# MotorBoard.net
KiCad netlist of a schematic drawn in Altium Designer
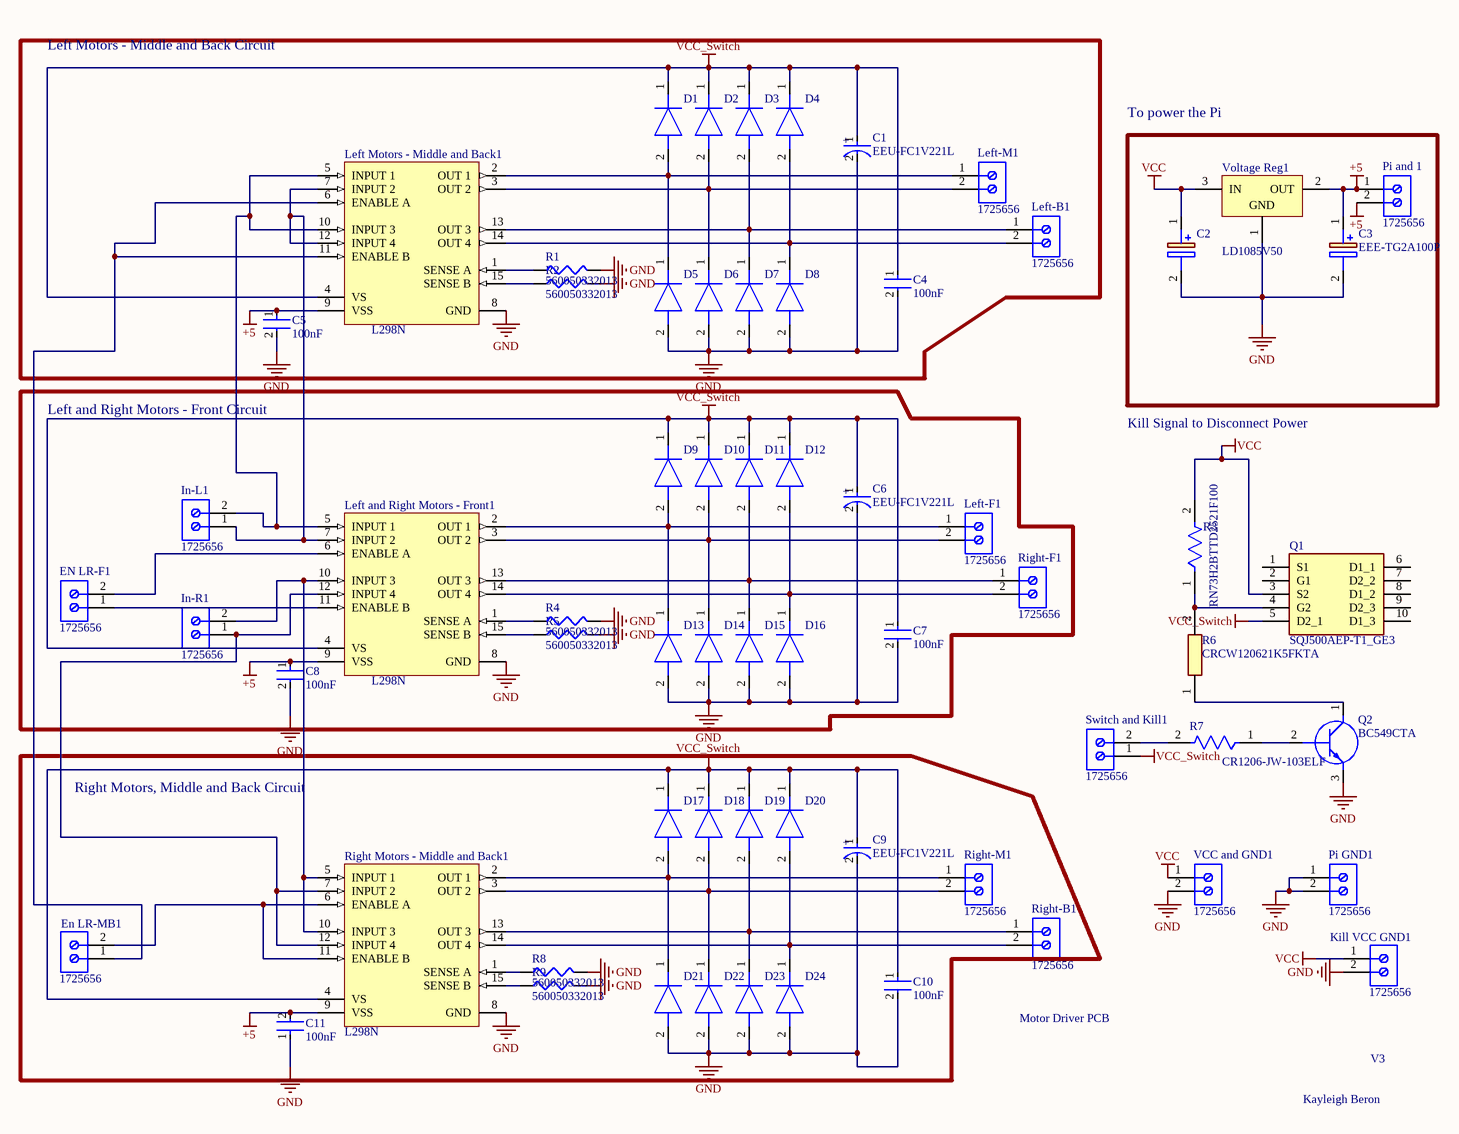
[diagram p0: MotorBoard.SchDoc]

(export (version "E")
  (design (tool "Eeschema 10.0.6"))
  (components
    (comp (ref "C1")
      (value "EEU-FC1V221L")
      (footprint "FP-EEU-FC1V221L-MFG")
      (description "CAP ALUM 220UF 20% 35V RADIAL")
      (fields
        (field (name "OCTOPART") "https://octopart.com/eeu-fc1v221l-panasonic-39478519")
        (field (name "MANUFACTURER") "Panasonic Electronic Components")
      )
      (libsource (lib "Altium Content Vault") (part "385ce6c70a3ab0aa1e866f00bd8ed49"))
    )
    (comp (ref "C2")
      (value "EEE-TG2A100P")
      (footprint "SamacSys:CAPAE830X1050N")
      (description "Capacitor Polarised")
      (fields (field (name "MOUSER PART NUMBER") "667-EEE-TG2A100P"))
      (libsource (lib "*") (part "EEE-TG2A100P"))
    )
    (comp (ref "C3")
      (value "EEE-TG2A100P")
      (footprint "SamacSys:CAPAE830X1050N")
      (description "Capacitor Polarised")
      (fields (field (name "MOUSER PART NUMBER") "667-EEE-TG2A100P"))
      (libsource (lib "*") (part "EEE-TG2A100P"))
    )
    (comp (ref "C4")
      (value "100nF")
      (footprint "FP-C2012-125-0_2-MFG")
      (description "Multilayer Ceramic Capacitors 100nF ±10% 50V X8R SMD 0805")
      (fields (field (name "TOLERANCE") "10%"))
      (libsource (lib "Altium Content Vault") (part "b4654b650e69147ec39a6b967a45e02"))
    )
    (comp (ref "C5")
      (value "100nF")
      (footprint "FP-C2012-125-0_2-MFG")
      (description "Multilayer Ceramic Capacitors 100nF ±10% 50V X8R SMD 0805")
      (fields (field (name "TOLERANCE") "10%"))
      (libsource (lib "Altium Content Vault") (part "b4654b650e69147ec39a6b967a45e02"))
    )
    (comp (ref "C6")
      (value "EEU-FC1V221L")
      (footprint "FP-EEU-FC1V221L-MFG")
      (description "CAP ALUM 220UF 20% 35V RADIAL")
      (fields
        (field (name "OCTOPART") "https://octopart.com/eeu-fc1v221l-panasonic-39478519")
        (field (name "MANUFACTURER") "Panasonic Electronic Components")
      )
      (libsource (lib "Altium Content Vault") (part "385ce6c70a3ab0aa1e866f00bd8ed49"))
    )
    (comp (ref "C7")
      (value "100nF")
      (footprint "FP-C2012-125-0_2-MFG")
      (description "Multilayer Ceramic Capacitors 100nF ±10% 50V X8R SMD 0805")
      (fields (field (name "TOLERANCE") "10%"))
      (libsource (lib "Altium Content Vault") (part "b4654b650e69147ec39a6b967a45e02"))
    )
    (comp (ref "C8")
      (value "100nF")
      (footprint "FP-C2012-125-0_2-MFG")
      (description "Multilayer Ceramic Capacitors 100nF ±10% 50V X8R SMD 0805")
      (fields (field (name "TOLERANCE") "10%"))
      (libsource (lib "Altium Content Vault") (part "b4654b650e69147ec39a6b967a45e02"))
    )
    (comp (ref "C9")
      (value "EEU-FC1V221L")
      (footprint "FP-EEU-FC1V221L-MFG")
      (description "CAP ALUM 220UF 20% 35V RADIAL")
      (fields
        (field (name "OCTOPART") "https://octopart.com/eeu-fc1v221l-panasonic-39478519")
        (field (name "MANUFACTURER") "Panasonic Electronic Components")
      )
      (libsource (lib "Altium Content Vault") (part "385ce6c70a3ab0aa1e866f00bd8ed49"))
    )
    (comp (ref "C10")
      (value "100nF")
      (footprint "FP-C2012-125-0_2-MFG")
      (description "Multilayer Ceramic Capacitors 100nF ±10% 50V X8R SMD 0805")
      (fields (field (name "TOLERANCE") "10%"))
      (libsource (lib "Altium Content Vault") (part "b4654b650e69147ec39a6b967a45e02"))
    )
    (comp (ref "C11")
      (value "100nF")
      (footprint "FP-C2012-125-0_2-MFG")
      (description "Multilayer Ceramic Capacitors 100nF ±10% 50V X8R SMD 0805")
      (fields (field (name "TOLERANCE") "10%"))
      (libsource (lib "Altium Content Vault") (part "b4654b650e69147ec39a6b967a45e02"))
    )
    (comp (ref "D1")
      (value "CMR1U-02M_TR13_PBFREE")
      (footprint "SamacSys:DIOM5226X262N")
      (description "Diode")
      (fields
        (field (name "MANUFACTURER_PART_NUMBER") "CMR1U-02M TR13 PBFREE")
        (field (name "MOUSER PART NUMBER") "610-CMR1U-02M")
      )
      (libsource (lib "*") (part "CMR1U-02M_TR13_PBFREE"))
    )
    (comp (ref "D2")
      (value "CMR1U-02M_TR13_PBFREE")
      (footprint "SamacSys:DIOM5226X262N")
      (description "Diode")
      (fields
        (field (name "MANUFACTURER_PART_NUMBER") "CMR1U-02M TR13 PBFREE")
        (field (name "MOUSER PART NUMBER") "610-CMR1U-02M")
      )
      (libsource (lib "*") (part "CMR1U-02M_TR13_PBFREE"))
    )
    (comp (ref "D3")
      (value "CMR1U-02M_TR13_PBFREE")
      (footprint "SamacSys:DIOM5226X262N")
      (description "Diode")
      (fields
        (field (name "MANUFACTURER_PART_NUMBER") "CMR1U-02M TR13 PBFREE")
        (field (name "MOUSER PART NUMBER") "610-CMR1U-02M")
      )
      (libsource (lib "*") (part "CMR1U-02M_TR13_PBFREE"))
    )
    (comp (ref "D4")
      (value "CMR1U-02M_TR13_PBFREE")
      (footprint "SamacSys:DIOM5226X262N")
      (description "Diode")
      (fields
        (field (name "MANUFACTURER_PART_NUMBER") "CMR1U-02M TR13 PBFREE")
        (field (name "MOUSER PART NUMBER") "610-CMR1U-02M")
      )
      (libsource (lib "*") (part "CMR1U-02M_TR13_PBFREE"))
    )
    (comp (ref "D5")
      (value "CMR1U-02M_TR13_PBFREE")
      (footprint "SamacSys:DIOM5226X262N")
      (description "Diode")
      (fields
        (field (name "MANUFACTURER_PART_NUMBER") "CMR1U-02M TR13 PBFREE")
        (field (name "MOUSER PART NUMBER") "610-CMR1U-02M")
      )
      (libsource (lib "*") (part "CMR1U-02M_TR13_PBFREE"))
    )
    (comp (ref "D6")
      (value "CMR1U-02M_TR13_PBFREE")
      (footprint "SamacSys:DIOM5226X262N")
      (description "Diode")
      (fields
        (field (name "MANUFACTURER_PART_NUMBER") "CMR1U-02M TR13 PBFREE")
        (field (name "MOUSER PART NUMBER") "610-CMR1U-02M")
      )
      (libsource (lib "*") (part "CMR1U-02M_TR13_PBFREE"))
    )
    (comp (ref "D7")
      (value "CMR1U-02M_TR13_PBFREE")
      (footprint "SamacSys:DIOM5226X262N")
      (description "Diode")
      (fields
        (field (name "MANUFACTURER_PART_NUMBER") "CMR1U-02M TR13 PBFREE")
        (field (name "MOUSER PART NUMBER") "610-CMR1U-02M")
      )
      (libsource (lib "*") (part "CMR1U-02M_TR13_PBFREE"))
    )
    (comp (ref "D8")
      (value "CMR1U-02M_TR13_PBFREE")
      (footprint "SamacSys:DIOM5226X262N")
      (description "Diode")
      (fields
        (field (name "MANUFACTURER_PART_NUMBER") "CMR1U-02M TR13 PBFREE")
        (field (name "MOUSER PART NUMBER") "610-CMR1U-02M")
      )
      (libsource (lib "*") (part "CMR1U-02M_TR13_PBFREE"))
    )
    (comp (ref "D9")
      (value "CMR1U-02M_TR13_PBFREE")
      (footprint "SamacSys:DIOM5226X262N")
      (description "Diode")
      (fields
        (field (name "MANUFACTURER_PART_NUMBER") "CMR1U-02M TR13 PBFREE")
        (field (name "MOUSER PART NUMBER") "610-CMR1U-02M")
      )
      (libsource (lib "*") (part "CMR1U-02M_TR13_PBFREE"))
    )
    (comp (ref "D10")
      (value "CMR1U-02M_TR13_PBFREE")
      (footprint "SamacSys:DIOM5226X262N")
      (description "Diode")
      (fields
        (field (name "MANUFACTURER_PART_NUMBER") "CMR1U-02M TR13 PBFREE")
        (field (name "MOUSER PART NUMBER") "610-CMR1U-02M")
      )
      (libsource (lib "*") (part "CMR1U-02M_TR13_PBFREE"))
    )
    (comp (ref "D11")
      (value "CMR1U-02M_TR13_PBFREE")
      (footprint "SamacSys:DIOM5226X262N")
      (description "Diode")
      (fields
        (field (name "MANUFACTURER_PART_NUMBER") "CMR1U-02M TR13 PBFREE")
        (field (name "MOUSER PART NUMBER") "610-CMR1U-02M")
      )
      (libsource (lib "*") (part "CMR1U-02M_TR13_PBFREE"))
    )
    (comp (ref "D12")
      (value "CMR1U-02M_TR13_PBFREE")
      (footprint "SamacSys:DIOM5226X262N")
      (description "Diode")
      (fields
        (field (name "MANUFACTURER_PART_NUMBER") "CMR1U-02M TR13 PBFREE")
        (field (name "MOUSER PART NUMBER") "610-CMR1U-02M")
      )
      (libsource (lib "*") (part "CMR1U-02M_TR13_PBFREE"))
    )
    (comp (ref "D13")
      (value "CMR1U-02M_TR13_PBFREE")
      (footprint "SamacSys:DIOM5226X262N")
      (description "Diode")
      (fields
        (field (name "MANUFACTURER_PART_NUMBER") "CMR1U-02M TR13 PBFREE")
        (field (name "MOUSER PART NUMBER") "610-CMR1U-02M")
      )
      (libsource (lib "*") (part "CMR1U-02M_TR13_PBFREE"))
    )
    (comp (ref "D14")
      (value "CMR1U-02M_TR13_PBFREE")
      (footprint "SamacSys:DIOM5226X262N")
      (description "Diode")
      (fields
        (field (name "MANUFACTURER_PART_NUMBER") "CMR1U-02M TR13 PBFREE")
        (field (name "MOUSER PART NUMBER") "610-CMR1U-02M")
      )
      (libsource (lib "*") (part "CMR1U-02M_TR13_PBFREE"))
    )
    (comp (ref "D15")
      (value "CMR1U-02M_TR13_PBFREE")
      (footprint "SamacSys:DIOM5226X262N")
      (description "Diode")
      (fields
        (field (name "MANUFACTURER_PART_NUMBER") "CMR1U-02M TR13 PBFREE")
        (field (name "MOUSER PART NUMBER") "610-CMR1U-02M")
      )
      (libsource (lib "*") (part "CMR1U-02M_TR13_PBFREE"))
    )
    (comp (ref "D16")
      (value "CMR1U-02M_TR13_PBFREE")
      (footprint "SamacSys:DIOM5226X262N")
      (description "Diode")
      (fields
        (field (name "MANUFACTURER_PART_NUMBER") "CMR1U-02M TR13 PBFREE")
        (field (name "MOUSER PART NUMBER") "610-CMR1U-02M")
      )
      (libsource (lib "*") (part "CMR1U-02M_TR13_PBFREE"))
    )
    (comp (ref "D17")
      (value "CMR1U-02M_TR13_PBFREE")
      (footprint "SamacSys:DIOM5226X262N")
      (description "Diode")
      (fields
        (field (name "MANUFACTURER_PART_NUMBER") "CMR1U-02M TR13 PBFREE")
        (field (name "MOUSER PART NUMBER") "610-CMR1U-02M")
      )
      (libsource (lib "*") (part "CMR1U-02M_TR13_PBFREE"))
    )
    (comp (ref "D18")
      (value "CMR1U-02M_TR13_PBFREE")
      (footprint "SamacSys:DIOM5226X262N")
      (description "Diode")
      (fields
        (field (name "MANUFACTURER_PART_NUMBER") "CMR1U-02M TR13 PBFREE")
        (field (name "MOUSER PART NUMBER") "610-CMR1U-02M")
      )
      (libsource (lib "*") (part "CMR1U-02M_TR13_PBFREE"))
    )
    (comp (ref "D19")
      (value "CMR1U-02M_TR13_PBFREE")
      (footprint "SamacSys:DIOM5226X262N")
      (description "Diode")
      (fields
        (field (name "MANUFACTURER_PART_NUMBER") "CMR1U-02M TR13 PBFREE")
        (field (name "MOUSER PART NUMBER") "610-CMR1U-02M")
      )
      (libsource (lib "*") (part "CMR1U-02M_TR13_PBFREE"))
    )
    (comp (ref "D20")
      (value "CMR1U-02M_TR13_PBFREE")
      (footprint "SamacSys:DIOM5226X262N")
      (description "Diode")
      (fields
        (field (name "MANUFACTURER_PART_NUMBER") "CMR1U-02M TR13 PBFREE")
        (field (name "MOUSER PART NUMBER") "610-CMR1U-02M")
      )
      (libsource (lib "*") (part "CMR1U-02M_TR13_PBFREE"))
    )
    (comp (ref "D21")
      (value "CMR1U-02M_TR13_PBFREE")
      (footprint "SamacSys:DIOM5226X262N")
      (description "Diode")
      (fields
        (field (name "MANUFACTURER_PART_NUMBER") "CMR1U-02M TR13 PBFREE")
        (field (name "MOUSER PART NUMBER") "610-CMR1U-02M")
      )
      (libsource (lib "*") (part "CMR1U-02M_TR13_PBFREE"))
    )
    (comp (ref "D22")
      (value "CMR1U-02M_TR13_PBFREE")
      (footprint "SamacSys:DIOM5226X262N")
      (description "Diode")
      (fields
        (field (name "MANUFACTURER_PART_NUMBER") "CMR1U-02M TR13 PBFREE")
        (field (name "MOUSER PART NUMBER") "610-CMR1U-02M")
      )
      (libsource (lib "*") (part "CMR1U-02M_TR13_PBFREE"))
    )
    (comp (ref "D23")
      (value "CMR1U-02M_TR13_PBFREE")
      (footprint "SamacSys:DIOM5226X262N")
      (description "Diode")
      (fields
        (field (name "MANUFACTURER_PART_NUMBER") "CMR1U-02M TR13 PBFREE")
        (field (name "MOUSER PART NUMBER") "610-CMR1U-02M")
      )
      (libsource (lib "*") (part "CMR1U-02M_TR13_PBFREE"))
    )
    (comp (ref "D24")
      (value "CMR1U-02M_TR13_PBFREE")
      (footprint "SamacSys:DIOM5226X262N")
      (description "Diode")
      (fields
        (field (name "MANUFACTURER_PART_NUMBER") "CMR1U-02M TR13 PBFREE")
        (field (name "MOUSER PART NUMBER") "610-CMR1U-02M")
      )
      (libsource (lib "*") (part "CMR1U-02M_TR13_PBFREE"))
    )
    (comp (ref "EN LR-F1")
      (value "1725656")
      (footprint "PHOE-1725656-2")
      (description "Male Header, Pitch 2.54 mm, 1 x 2 Position, Height 9 mm, Tail Length 3.5 mm")
      (fields (field (name "MANUFACTURER") "Phoenix Contact"))
      (libsource (lib "Altium Content Vault") (part "CN-1P-F-TB2"))
    )
    (comp (ref "En LR-MB1")
      (value "1725656")
      (footprint "PHOE-1725656-2")
      (description "Male Header, Pitch 2.54 mm, 1 x 2 Position, Height 9 mm, Tail Length 3.5 mm")
      (fields (field (name "MANUFACTURER") "Phoenix Contact"))
      (libsource (lib "Altium Content Vault") (part "CN-1P-F-TB2"))
    )
    (comp (ref "In-L1")
      (value "1725656")
      (footprint "PHOE-1725656-2")
      (description "Male Header, Pitch 2.54 mm, 1 x 2 Position, Height 9 mm, Tail Length 3.5 mm")
      (fields (field (name "MANUFACTURER") "Phoenix Contact"))
      (libsource (lib "Altium Content Vault") (part "CN-1P-F-TB2"))
    )
    (comp (ref "In-R1")
      (value "1725656")
      (footprint "PHOE-1725656-2")
      (description "Male Header, Pitch 2.54 mm, 1 x 2 Position, Height 9 mm, Tail Length 3.5 mm")
      (fields (field (name "MANUFACTURER") "Phoenix Contact"))
      (libsource (lib "Altium Content Vault") (part "CN-1P-F-TB2"))
    )
    (comp (ref "Kill VCC GND1")
      (value "1725656")
      (footprint "PHOE-1725656-2")
      (description "Male Header, Pitch 2.54 mm, 1 x 2 Position, Height 9 mm, Tail Length 3.5 mm")
      (fields (field (name "MANUFACTURER") "Phoenix Contact"))
      (libsource (lib "Altium Content Vault") (part "CN-1P-F-TB2"))
    )
    (comp (ref "Left and Right Motors - Front1")
      (value "L298N")
      (footprint "STM-FM-15")
      (description "Dual Full-Bridge Driver, 4.8 to 46 V, -40 to 150 degC, 15-Pin FM (MW 15L), RoHS, Tube")
      (fields (field (name "MANUFACTURER") "STMicroelectronics") (field (name "PARTNUMBER") "L298"))
      (libsource (lib "Altium Content Vault") (part "STM-L298-15"))
    )
    (comp (ref "Left Motors - Middle and Back1")
      (value "L298N")
      (footprint "STM-FM-15")
      (description "Dual Full-Bridge Driver, 4.8 to 46 V, -40 to 150 degC, 15-Pin FM (MW 15L), RoHS, Tube")
      (fields (field (name "MANUFACTURER") "STMicroelectronics") (field (name "PARTNUMBER") "L298"))
      (libsource (lib "Altium Content Vault") (part "STM-L298-15"))
    )
    (comp (ref "Left-B1")
      (value "1725656")
      (footprint "PHOE-1725656-2")
      (description "Male Header, Pitch 2.54 mm, 1 x 2 Position, Height 9 mm, Tail Length 3.5 mm")
      (fields (field (name "MANUFACTURER") "Phoenix Contact"))
      (libsource (lib "Altium Content Vault") (part "CN-1P-F-TB2"))
    )
    (comp (ref "Left-F1")
      (value "1725656")
      (footprint "PHOE-1725656-2")
      (description "Male Header, Pitch 2.54 mm, 1 x 2 Position, Height 9 mm, Tail Length 3.5 mm")
      (fields (field (name "MANUFACTURER") "Phoenix Contact"))
      (libsource (lib "Altium Content Vault") (part "CN-1P-F-TB2"))
    )
    (comp (ref "Left-M1")
      (value "1725656")
      (footprint "PHOE-1725656-2")
      (description "Male Header, Pitch 2.54 mm, 1 x 2 Position, Height 9 mm, Tail Length 3.5 mm")
      (fields (field (name "MANUFACTURER") "Phoenix Contact"))
      (libsource (lib "Altium Content Vault") (part "CN-1P-F-TB2"))
    )
    (comp (ref "Pi and 1")
      (value "1725656")
      (footprint "PHOE-1725656-2")
      (description "Male Header, Pitch 2.54 mm, 1 x 2 Position, Height 9 mm, Tail Length 3.5 mm")
      (fields (field (name "MANUFACTURER") "Phoenix Contact"))
      (libsource (lib "Altium Content Vault") (part "CN-1P-F-TB2"))
    )
    (comp (ref "Pi GND1")
      (value "1725656")
      (footprint "PHOE-1725656-2")
      (description "Male Header, Pitch 2.54 mm, 1 x 2 Position, Height 9 mm, Tail Length 3.5 mm")
      (fields (field (name "MANUFACTURER") "Phoenix Contact"))
      (libsource (lib "Altium Content Vault") (part "CN-1P-F-TB2"))
    )
    (comp (ref "Q1")
      (value "SQJ500AEP-T1_GE3")
      (footprint "SamacSys:SQJB02ELPT1_GE3")
      (description "MOSFET (N-Channel)")
      (fields (field (name "MOUSER PART NUMBER") "78-SQJ500AEP-T1_GE3"))
      (libsource (lib "*") (part "SQJ500AEP-T1_GE3"))
    )
    (comp (ref "Q2")
      (value "BC549CTA")
      (footprint "SamacSys:BC33740TA")
      (description "Transistor BJT NPN")
      (fields (field (name "MOUSER PART NUMBER") "512-BC549CTA"))
      (libsource (lib "*") (part "BC549CTA"))
    )
    (comp (ref "R1")
      (value "560050332013")
      (footprint "WRIS-KSKE_1206_L3.1W1.6H0.6")
      (description "560050332013 Res, R5, 1%, 0.5W, Thick Film, 1206 Rohs Compliant: Yes")
      (libsource (lib "Altium Content Vault") (part "Resistor"))
    )
    (comp (ref "R2")
      (value "560050332013")
      (footprint "WRIS-KSKE_1206_L3.1W1.6H0.6")
      (description "560050332013 Res, R5, 1%, 0.5W, Thick Film, 1206 Rohs Compliant: Yes")
      (libsource (lib "Altium Content Vault") (part "Resistor"))
    )
    (comp (ref "R3")
      (value "RN73H2BTTD2521F100")
      (footprint "FP-CR1206-IPC_B")
      (description "Thick Film Chip Resistors 1206 10kΩ 0.25W 5% 200ppm/°C")
      (fields (field (name "TOLERANCE") "5%"))
      (libsource (lib "Altium Content Vault") (part "1029c3af85768c4190bb7ad29bc67b5"))
    )
    (comp (ref "R4")
      (value "560050332013")
      (footprint "WRIS-KSKE_1206_L3.1W1.6H0.6")
      (description "560050332013 Res, R5, 1%, 0.5W, Thick Film, 1206 Rohs Compliant: Yes")
      (libsource (lib "Altium Content Vault") (part "Resistor"))
    )
    (comp (ref "R5")
      (value "560050332013")
      (footprint "WRIS-KSKE_1206_L3.1W1.6H0.6")
      (description "560050332013 Res, R5, 1%, 0.5W, Thick Film, 1206 Rohs Compliant: Yes")
      (libsource (lib "Altium Content Vault") (part "Resistor"))
    )
    (comp (ref "R6")
      (value "CRCW120621K5FKTA")
      (footprint "SamacSys:RESC3216X60N")
      (description "Resistor")
      (fields (field (name "MOUSER PART NUMBER") "71-CRCW1206-21.5K"))
      (libsource (lib "*") (part "CRCW120621K5FKTA"))
    )
    (comp (ref "R7")
      (value "CR1206-JW-103ELF")
      (footprint "FP-CR1206-IPC_B")
      (description "Thick Film Chip Resistors 1206 10kΩ 0.25W 5% 200ppm/°C")
      (fields (field (name "TOLERANCE") "5%"))
      (libsource (lib "Altium Content Vault") (part "1029c3af85768c4190bb7ad29bc67b5"))
    )
    (comp (ref "R8")
      (value "560050332013")
      (footprint "WRIS-KSKE_1206_L3.1W1.6H0.6")
      (description "560050332013 Res, R5, 1%, 0.5W, Thick Film, 1206 Rohs Compliant: Yes")
      (libsource (lib "Altium Content Vault") (part "Resistor"))
    )
    (comp (ref "R9")
      (value "560050332013")
      (footprint "WRIS-KSKE_1206_L3.1W1.6H0.6")
      (description "560050332013 Res, R5, 1%, 0.5W, Thick Film, 1206 Rohs Compliant: Yes")
      (libsource (lib "Altium Content Vault") (part "Resistor"))
    )
    (comp (ref "Right Motors - Middle and Back1")
      (value "L298N")
      (footprint "STM-FM-15")
      (description "Dual Full-Bridge Driver, 4.8 to 46 V, -40 to 150 degC, 15-Pin FM (MW 15L), RoHS, Tube")
      (fields (field (name "MANUFACTURER") "STMicroelectronics") (field (name "PARTNUMBER") "L298"))
      (libsource (lib "Altium Content Vault") (part "STM-L298-15"))
    )
    (comp (ref "Right-B1")
      (value "1725656")
      (footprint "PHOE-1725656-2")
      (description "Male Header, Pitch 2.54 mm, 1 x 2 Position, Height 9 mm, Tail Length 3.5 mm")
      (fields (field (name "MANUFACTURER") "Phoenix Contact"))
      (libsource (lib "Altium Content Vault") (part "CN-1P-F-TB2"))
    )
    (comp (ref "Right-F1")
      (value "1725656")
      (footprint "PHOE-1725656-2")
      (description "Male Header, Pitch 2.54 mm, 1 x 2 Position, Height 9 mm, Tail Length 3.5 mm")
      (fields (field (name "MANUFACTURER") "Phoenix Contact"))
      (libsource (lib "Altium Content Vault") (part "CN-1P-F-TB2"))
    )
    (comp (ref "Right-M1")
      (value "1725656")
      (footprint "PHOE-1725656-2")
      (description "Male Header, Pitch 2.54 mm, 1 x 2 Position, Height 9 mm, Tail Length 3.5 mm")
      (fields (field (name "MANUFACTURER") "Phoenix Contact"))
      (libsource (lib "Altium Content Vault") (part "CN-1P-F-TB2"))
    )
    (comp (ref "Switch and Kill1")
      (value "1725656")
      (footprint "PHOE-1725656-2")
      (description "Male Header, Pitch 2.54 mm, 1 x 2 Position, Height 9 mm, Tail Length 3.5 mm")
      (fields (field (name "MANUFACTURER") "Phoenix Contact"))
      (libsource (lib "Altium Content Vault") (part "CN-1P-F-TB2"))
    )
    (comp (ref "VCC and GND1")
      (value "1725656")
      (footprint "PHOE-1725656-2")
      (description "Male Header, Pitch 2.54 mm, 1 x 2 Position, Height 9 mm, Tail Length 3.5 mm")
      (fields (field (name "MANUFACTURER") "Phoenix Contact"))
      (libsource (lib "Altium Content Vault") (part "CN-1P-F-TB2"))
    )
    (comp (ref "Voltage Reg1")
      (value "LD1085V50")
      (footprint "TO220")
      (description "3A, Low Drop Positive Voltage Regulator, 5V, 3-Pin TO-220")
      (libsource (lib "Altium Content Vault") (part "PM-REG-LD1085-SIL3"))
    )
  )
  (nets
    (net (code "1") (name "+5") (class "Default")
      (node (ref "C11") (pin "2") (pinfunction "2_2") (pintype "passive"))
      (node (ref "C3") (pin "1") (pinfunction "+_1") (pintype "passive"))
      (node (ref "C5") (pin "1") (pinfunction "1_1") (pintype "passive"))
      (node (ref "C8") (pin "1") (pinfunction "1_1") (pintype "passive"))
      (node (ref "Left Motors - Middle and Back1") (pin "9") (pinfunction "VSS_9") (pintype "power_in"))
      (node (ref "Left and Right Motors - Front1") (pin "9") (pinfunction "VSS_9") (pintype "power_in"))
      (node (ref "Pi and 1") (pin "1") (pinfunction "1_1") (pintype "passive"))
      (node (ref "Pi and 1") (pin "2") (pinfunction "2_2") (pintype "passive"))
      (node (ref "Right Motors - Middle and Back1") (pin "9") (pinfunction "VSS_9") (pintype "power_in"))
      (node (ref "Voltage Reg1") (pin "2") (pinfunction "OUT_2") (pintype "power_in"))
    )
    (net (code "2") (name "GND") (class "Default")
      (node (ref "C1") (pin "2") (pinfunction "A_2") (pintype "passive"))
      (node (ref "C10") (pin "2") (pinfunction "2_2") (pintype "passive"))
      (node (ref "C11") (pin "1") (pinfunction "1_1") (pintype "passive"))
      (node (ref "C2") (pin "2") (pinfunction "-_2") (pintype "passive"))
      (node (ref "C3") (pin "2") (pinfunction "-_2") (pintype "passive"))
      (node (ref "C4") (pin "2") (pinfunction "2_2") (pintype "passive"))
      (node (ref "C5") (pin "2") (pinfunction "2_2") (pintype "passive"))
      (node (ref "C6") (pin "2") (pinfunction "A_2") (pintype "passive"))
      (node (ref "C7") (pin "2") (pinfunction "2_2") (pintype "passive"))
      (node (ref "C8") (pin "2") (pinfunction "2_2") (pintype "passive"))
      (node (ref "C9") (pin "2") (pinfunction "A_2") (pintype "passive"))
      (node (ref "D13") (pin "2") (pinfunction "A_2") (pintype "passive"))
      (node (ref "D14") (pin "2") (pinfunction "A_2") (pintype "passive"))
      (node (ref "D15") (pin "2") (pinfunction "A_2") (pintype "passive"))
      (node (ref "D16") (pin "2") (pinfunction "A_2") (pintype "passive"))
      (node (ref "D21") (pin "2") (pinfunction "A_2") (pintype "passive"))
      (node (ref "D22") (pin "2") (pinfunction "A_2") (pintype "passive"))
      (node (ref "D23") (pin "2") (pinfunction "A_2") (pintype "passive"))
      (node (ref "D24") (pin "2") (pinfunction "A_2") (pintype "passive"))
      (node (ref "D5") (pin "2") (pinfunction "A_2") (pintype "passive"))
      (node (ref "D6") (pin "2") (pinfunction "A_2") (pintype "passive"))
      (node (ref "D7") (pin "2") (pinfunction "A_2") (pintype "passive"))
      (node (ref "D8") (pin "2") (pinfunction "A_2") (pintype "passive"))
      (node (ref "Kill VCC GND1") (pin "2") (pinfunction "2_2") (pintype "passive"))
      (node (ref "Left Motors - Middle and Back1") (pin "8") (pinfunction "GND_8") (pintype "power_in"))
      (node (ref "Left and Right Motors - Front1") (pin "8") (pinfunction "GND_8") (pintype "power_in"))
      (node (ref "Pi GND1") (pin "1") (pinfunction "1_1") (pintype "passive"))
      (node (ref "Pi GND1") (pin "2") (pinfunction "2_2") (pintype "passive"))
      (node (ref "Q2") (pin "3") (pinfunction "E_3") (pintype "passive"))
      (node (ref "R1") (pin "2") (pinfunction "2_2") (pintype "passive"))
      (node (ref "R2") (pin "2") (pinfunction "2_2") (pintype "passive"))
      (node (ref "R4") (pin "2") (pinfunction "2_2") (pintype "passive"))
      (node (ref "R5") (pin "2") (pinfunction "2_2") (pintype "passive"))
      (node (ref "R8") (pin "2") (pinfunction "2_2") (pintype "passive"))
      (node (ref "R9") (pin "2") (pinfunction "2_2") (pintype "passive"))
      (node (ref "Right Motors - Middle and Back1") (pin "8") (pinfunction "GND_8") (pintype "power_in"))
      (node (ref "VCC and GND1") (pin "2") (pinfunction "2_2") (pintype "passive"))
      (node (ref "Voltage Reg1") (pin "1") (pinfunction "GND_1") (pintype "power_in"))
    )
    (net (code "3") (name "Net-(D1-A)") (class "Default")
      (node (ref "D1") (pin "2") (pinfunction "A_2") (pintype "passive"))
      (node (ref "D5") (pin "1") (pinfunction "K_1") (pintype "passive"))
      (node (ref "Left Motors - Middle and Back1") (pin "2") (pinfunction "OUT_1_2") (pintype "output"))
      (node (ref "Left-M1") (pin "1") (pinfunction "1_1") (pintype "passive"))
    )
    (net (code "4") (name "Net-(D2-A)") (class "Default")
      (node (ref "D2") (pin "2") (pinfunction "A_2") (pintype "passive"))
      (node (ref "D6") (pin "1") (pinfunction "K_1") (pintype "passive"))
      (node (ref "Left Motors - Middle and Back1") (pin "3") (pinfunction "OUT_2_3") (pintype "output"))
      (node (ref "Left-M1") (pin "2") (pinfunction "2_2") (pintype "passive"))
    )
    (net (code "5") (name "Net-(D3-A)") (class "Default")
      (node (ref "D3") (pin "2") (pinfunction "A_2") (pintype "passive"))
      (node (ref "D7") (pin "1") (pinfunction "K_1") (pintype "passive"))
      (node (ref "Left Motors - Middle and Back1") (pin "13") (pinfunction "OUT_3_13") (pintype "output"))
      (node (ref "Left-B1") (pin "1") (pinfunction "1_1") (pintype "passive"))
    )
    (net (code "6") (name "Net-(D4-A)") (class "Default")
      (node (ref "D4") (pin "2") (pinfunction "A_2") (pintype "passive"))
      (node (ref "D8") (pin "1") (pinfunction "K_1") (pintype "passive"))
      (node (ref "Left Motors - Middle and Back1") (pin "14") (pinfunction "OUT_4_14") (pintype "output"))
      (node (ref "Left-B1") (pin "2") (pinfunction "2_2") (pintype "passive"))
    )
    (net (code "7") (name "Net-(D10-A)") (class "Default")
      (node (ref "D10") (pin "2") (pinfunction "A_2") (pintype "passive"))
      (node (ref "D14") (pin "1") (pinfunction "K_1") (pintype "passive"))
      (node (ref "Left and Right Motors - Front1") (pin "3") (pinfunction "OUT_2_3") (pintype "output"))
      (node (ref "Left-F1") (pin "2") (pinfunction "2_2") (pintype "passive"))
    )
    (net (code "8") (name "Net-(D11-A)") (class "Default")
      (node (ref "D11") (pin "2") (pinfunction "A_2") (pintype "passive"))
      (node (ref "D15") (pin "1") (pinfunction "K_1") (pintype "passive"))
      (node (ref "Left and Right Motors - Front1") (pin "13") (pinfunction "OUT_3_13") (pintype "output"))
      (node (ref "Right-F1") (pin "1") (pinfunction "1_1") (pintype "passive"))
    )
    (net (code "9") (name "Net-(D12-A)") (class "Default")
      (node (ref "D12") (pin "2") (pinfunction "A_2") (pintype "passive"))
      (node (ref "D16") (pin "1") (pinfunction "K_1") (pintype "passive"))
      (node (ref "Left and Right Motors - Front1") (pin "14") (pinfunction "OUT_4_14") (pintype "output"))
      (node (ref "Right-F1") (pin "2") (pinfunction "2_2") (pintype "passive"))
    )
    (net (code "10") (name "Net-(D13-K)") (class "Default")
      (node (ref "D13") (pin "1") (pinfunction "K_1") (pintype "passive"))
      (node (ref "D9") (pin "2") (pinfunction "A_2") (pintype "passive"))
      (node (ref "Left and Right Motors - Front1") (pin "2") (pinfunction "OUT_1_2") (pintype "output"))
      (node (ref "Left-F1") (pin "1") (pinfunction "1_1") (pintype "passive"))
    )
    (net (code "11") (name "Net-(D17-A)") (class "Default")
      (node (ref "D17") (pin "2") (pinfunction "A_2") (pintype "passive"))
      (node (ref "D21") (pin "1") (pinfunction "K_1") (pintype "passive"))
      (node (ref "Right Motors - Middle and Back1") (pin "2") (pinfunction "OUT_1_2") (pintype "output"))
      (node (ref "Right-M1") (pin "1") (pinfunction "1_1") (pintype "passive"))
    )
    (net (code "12") (name "Net-(D18-A)") (class "Default")
      (node (ref "D18") (pin "2") (pinfunction "A_2") (pintype "passive"))
      (node (ref "D22") (pin "1") (pinfunction "K_1") (pintype "passive"))
      (node (ref "Right Motors - Middle and Back1") (pin "3") (pinfunction "OUT_2_3") (pintype "output"))
      (node (ref "Right-M1") (pin "2") (pinfunction "2_2") (pintype "passive"))
    )
    (net (code "13") (name "Net-(D19-A)") (class "Default")
      (node (ref "D19") (pin "2") (pinfunction "A_2") (pintype "passive"))
      (node (ref "D23") (pin "1") (pinfunction "K_1") (pintype "passive"))
      (node (ref "Right Motors - Middle and Back1") (pin "13") (pinfunction "OUT_3_13") (pintype "output"))
      (node (ref "Right-B1") (pin "1") (pinfunction "1_1") (pintype "passive"))
    )
    (net (code "14") (name "Net-(D20-A)") (class "Default")
      (node (ref "D20") (pin "2") (pinfunction "A_2") (pintype "passive"))
      (node (ref "D24") (pin "1") (pinfunction "K_1") (pintype "passive"))
      (node (ref "Right Motors - Middle and Back1") (pin "14") (pinfunction "OUT_4_14") (pintype "output"))
      (node (ref "Right-B1") (pin "2") (pinfunction "2_2") (pintype "passive"))
    )
    (net (code "15") (name "Net-(Left Motors - Middle and Back1-ENABLE_A)") (class "Default")
      (node (ref "En LR-MB1") (pin "1") (pinfunction "1_1") (pintype "passive"))
      (node (ref "Left Motors - Middle and Back1") (pin "11") (pinfunction "ENABLE_B_11") (pintype "input"))
      (node (ref "Left Motors - Middle and Back1") (pin "6") (pinfunction "ENABLE_A_6") (pintype "input"))
    )
    (net (code "16") (name "Net-(Left Motors - Middle and Back1-INPUT_1)") (class "Default")
      (node (ref "In-L1") (pin "2") (pinfunction "2_2") (pintype "passive"))
      (node (ref "Left Motors - Middle and Back1") (pin "10") (pinfunction "INPUT_3_10") (pintype "input"))
      (node (ref "Left Motors - Middle and Back1") (pin "5") (pinfunction "INPUT_1_5") (pintype "input"))
      (node (ref "Left and Right Motors - Front1") (pin "5") (pinfunction "INPUT_1_5") (pintype "input"))
    )
    (net (code "17") (name "Net-(Left Motors - Middle and Back1-INPUT_2)") (class "Default")
      (node (ref "In-L1") (pin "1") (pinfunction "1_1") (pintype "passive"))
      (node (ref "Left Motors - Middle and Back1") (pin "12") (pinfunction "INPUT_4_12") (pintype "input"))
      (node (ref "Left Motors - Middle and Back1") (pin "7") (pinfunction "INPUT_2_7") (pintype "input"))
      (node (ref "Left and Right Motors - Front1") (pin "7") (pinfunction "INPUT_2_7") (pintype "input"))
    )
    (net (code "18") (name "Net-(Left Motors - Middle and Back1-SENSE_A)") (class "Default")
      (node (ref "Left Motors - Middle and Back1") (pin "1") (pinfunction "SENSE_A_1") (pintype "input"))
      (node (ref "R1") (pin "1") (pinfunction "1_1") (pintype "passive"))
    )
    (net (code "19") (name "Net-(Left Motors - Middle and Back1-SENSE_B)") (class "Default")
      (node (ref "Left Motors - Middle and Back1") (pin "15") (pinfunction "SENSE_B_15") (pintype "input"))
      (node (ref "R2") (pin "1") (pinfunction "1_1") (pintype "passive"))
    )
    (net (code "20") (name "Net-(Left and Right Motors - Front1-ENABLE_A)") (class "Default")
      (node (ref "EN LR-F1") (pin "2") (pinfunction "2_2") (pintype "passive"))
      (node (ref "Left and Right Motors - Front1") (pin "6") (pinfunction "ENABLE_A_6") (pintype "input"))
    )
    (net (code "21") (name "Net-(Left and Right Motors - Front1-ENABLE_B)") (class "Default")
      (node (ref "EN LR-F1") (pin "1") (pinfunction "1_1") (pintype "passive"))
      (node (ref "Left and Right Motors - Front1") (pin "11") (pinfunction "ENABLE_B_11") (pintype "input"))
    )
    (net (code "22") (name "Net-(Left and Right Motors - Front1-INPUT_3)") (class "Default")
      (node (ref "In-R1") (pin "2") (pinfunction "2_2") (pintype "passive"))
      (node (ref "Left and Right Motors - Front1") (pin "10") (pinfunction "INPUT_3_10") (pintype "input"))
      (node (ref "Right Motors - Middle and Back1") (pin "10") (pinfunction "INPUT_3_10") (pintype "input"))
      (node (ref "Right Motors - Middle and Back1") (pin "5") (pinfunction "INPUT_1_5") (pintype "input"))
    )
    (net (code "23") (name "Net-(Left and Right Motors - Front1-INPUT_4)") (class "Default")
      (node (ref "In-R1") (pin "1") (pinfunction "1_1") (pintype "passive"))
      (node (ref "Left and Right Motors - Front1") (pin "12") (pinfunction "INPUT_4_12") (pintype "input"))
      (node (ref "Right Motors - Middle and Back1") (pin "12") (pinfunction "INPUT_4_12") (pintype "input"))
      (node (ref "Right Motors - Middle and Back1") (pin "7") (pinfunction "INPUT_2_7") (pintype "input"))
    )
    (net (code "24") (name "Net-(Left and Right Motors - Front1-SENSE_A)") (class "Default")
      (node (ref "Left and Right Motors - Front1") (pin "1") (pinfunction "SENSE_A_1") (pintype "input"))
      (node (ref "R4") (pin "1") (pinfunction "1_1") (pintype "passive"))
    )
    (net (code "25") (name "Net-(Left and Right Motors - Front1-SENSE_B)") (class "Default")
      (node (ref "Left and Right Motors - Front1") (pin "15") (pinfunction "SENSE_B_15") (pintype "input"))
      (node (ref "R5") (pin "1") (pinfunction "1_1") (pintype "passive"))
    )
    (net (code "26") (name "Net-(Q1-G2)") (class "Default")
      (node (ref "Q1") (pin "4") (pinfunction "G2_4") (pintype "passive"))
      (node (ref "R3") (pin "1") (pinfunction "1_1") (pintype "passive"))
      (node (ref "R6") (pin "2") (pinfunction "2_2") (pintype "passive"))
    )
    (net (code "27") (name "Net-(Q2-B)") (class "Default")
      (node (ref "Q2") (pin "2") (pinfunction "B_2") (pintype "passive"))
      (node (ref "R7") (pin "1") (pinfunction "1_1") (pintype "passive"))
    )
    (net (code "28") (name "Net-(Q2-C)") (class "Default")
      (node (ref "Q2") (pin "1") (pinfunction "C_1") (pintype "passive"))
      (node (ref "R6") (pin "1") (pinfunction "1_1") (pintype "passive"))
    )
    (net (code "29") (name "Net-(R7-Pad2)") (class "Default")
      (node (ref "R7") (pin "2") (pinfunction "2_2") (pintype "passive"))
      (node (ref "Switch and Kill1") (pin "2") (pinfunction "2_2") (pintype "passive"))
    )
    (net (code "30") (name "Net-(Right Motors - Middle and Back1-ENABLE_A)") (class "Default")
      (node (ref "En LR-MB1") (pin "2") (pinfunction "2_2") (pintype "passive"))
      (node (ref "Right Motors - Middle and Back1") (pin "11") (pinfunction "ENABLE_B_11") (pintype "input"))
      (node (ref "Right Motors - Middle and Back1") (pin "6") (pinfunction "ENABLE_A_6") (pintype "input"))
    )
    (net (code "31") (name "Net-(Right Motors - Middle and Back1-SENSE_A)") (class "Default")
      (node (ref "R8") (pin "1") (pinfunction "1_1") (pintype "passive"))
      (node (ref "Right Motors - Middle and Back1") (pin "1") (pinfunction "SENSE_A_1") (pintype "input"))
    )
    (net (code "32") (name "Net-(Right Motors - Middle and Back1-SENSE_B)") (class "Default")
      (node (ref "R9") (pin "1") (pinfunction "1_1") (pintype "passive"))
      (node (ref "Right Motors - Middle and Back1") (pin "15") (pinfunction "SENSE_B_15") (pintype "input"))
    )
    (net (code "33") (name "VCC") (class "Default")
      (node (ref "C2") (pin "1") (pinfunction "+_1") (pintype "passive"))
      (node (ref "Kill VCC GND1") (pin "1") (pinfunction "1_1") (pintype "passive"))
      (node (ref "Q1") (pin "3") (pinfunction "S2_3") (pintype "passive"))
      (node (ref "R3") (pin "2") (pinfunction "2_2") (pintype "passive"))
      (node (ref "VCC and GND1") (pin "1") (pinfunction "1_1") (pintype "passive"))
      (node (ref "Voltage Reg1") (pin "3") (pinfunction "IN_3") (pintype "power_in"))
    )
    (net (code "34") (name "VCC_Switch") (class "Default")
      (node (ref "C1") (pin "1") (pinfunction "C_1") (pintype "passive"))
      (node (ref "C10") (pin "1") (pinfunction "1_1") (pintype "passive"))
      (node (ref "C4") (pin "1") (pinfunction "1_1") (pintype "passive"))
      (node (ref "C6") (pin "1") (pinfunction "C_1") (pintype "passive"))
      (node (ref "C7") (pin "1") (pinfunction "1_1") (pintype "passive"))
      (node (ref "C9") (pin "1") (pinfunction "C_1") (pintype "passive"))
      (node (ref "D1") (pin "1") (pinfunction "K_1") (pintype "passive"))
      (node (ref "D10") (pin "1") (pinfunction "K_1") (pintype "passive"))
      (node (ref "D11") (pin "1") (pinfunction "K_1") (pintype "passive"))
      (node (ref "D12") (pin "1") (pinfunction "K_1") (pintype "passive"))
      (node (ref "D17") (pin "1") (pinfunction "K_1") (pintype "passive"))
      (node (ref "D18") (pin "1") (pinfunction "K_1") (pintype "passive"))
      (node (ref "D19") (pin "1") (pinfunction "K_1") (pintype "passive"))
      (node (ref "D2") (pin "1") (pinfunction "K_1") (pintype "passive"))
      (node (ref "D20") (pin "1") (pinfunction "K_1") (pintype "passive"))
      (node (ref "D3") (pin "1") (pinfunction "K_1") (pintype "passive"))
      (node (ref "D4") (pin "1") (pinfunction "K_1") (pintype "passive"))
      (node (ref "D9") (pin "1") (pinfunction "K_1") (pintype "passive"))
      (node (ref "Left Motors - Middle and Back1") (pin "4") (pinfunction "VS_4") (pintype "power_in"))
      (node (ref "Left and Right Motors - Front1") (pin "4") (pinfunction "VS_4") (pintype "power_in"))
      (node (ref "Q1") (pin "5") (pinfunction "D2_1_5") (pintype "passive"))
      (node (ref "Right Motors - Middle and Back1") (pin "4") (pinfunction "VS_4") (pintype "power_in"))
      (node (ref "Switch and Kill1") (pin "1") (pinfunction "1_1") (pintype "passive"))
    )
    (net (code "35") (name "unconnected-(Q1-D1_1-Pad6)") (class "Default")
      (node (ref "Q1") (pin "6") (pinfunction "D1_1_6") (pintype "passive"))
    )
    (net (code "36") (name "unconnected-(Q1-D1_2-Pad8)") (class "Default")
      (node (ref "Q1") (pin "8") (pinfunction "D1_2_8") (pintype "passive"))
    )
    (net (code "37") (name "unconnected-(Q1-D1_3-Pad10)") (class "Default")
      (node (ref "Q1") (pin "10") (pinfunction "D1_3_10") (pintype "passive"))
    )
    (net (code "38") (name "unconnected-(Q1-D2_2-Pad7)") (class "Default")
      (node (ref "Q1") (pin "7") (pinfunction "D2_2_7") (pintype "passive"))
    )
    (net (code "39") (name "unconnected-(Q1-D2_3-Pad9)") (class "Default")
      (node (ref "Q1") (pin "9") (pinfunction "D2_3_9") (pintype "passive"))
    )
    (net (code "40") (name "unconnected-(Q1-G1-Pad2)") (class "Default")
      (node (ref "Q1") (pin "2") (pinfunction "G1_2") (pintype "passive"))
    )
    (net (code "41") (name "unconnected-(Q1-S1-Pad1)") (class "Default")
      (node (ref "Q1") (pin "1") (pinfunction "S1_1") (pintype "passive"))
    )
  )
)
